# VCO_4046_v_2.net
KiCad netlist of a schematic drawn in EasyEDA
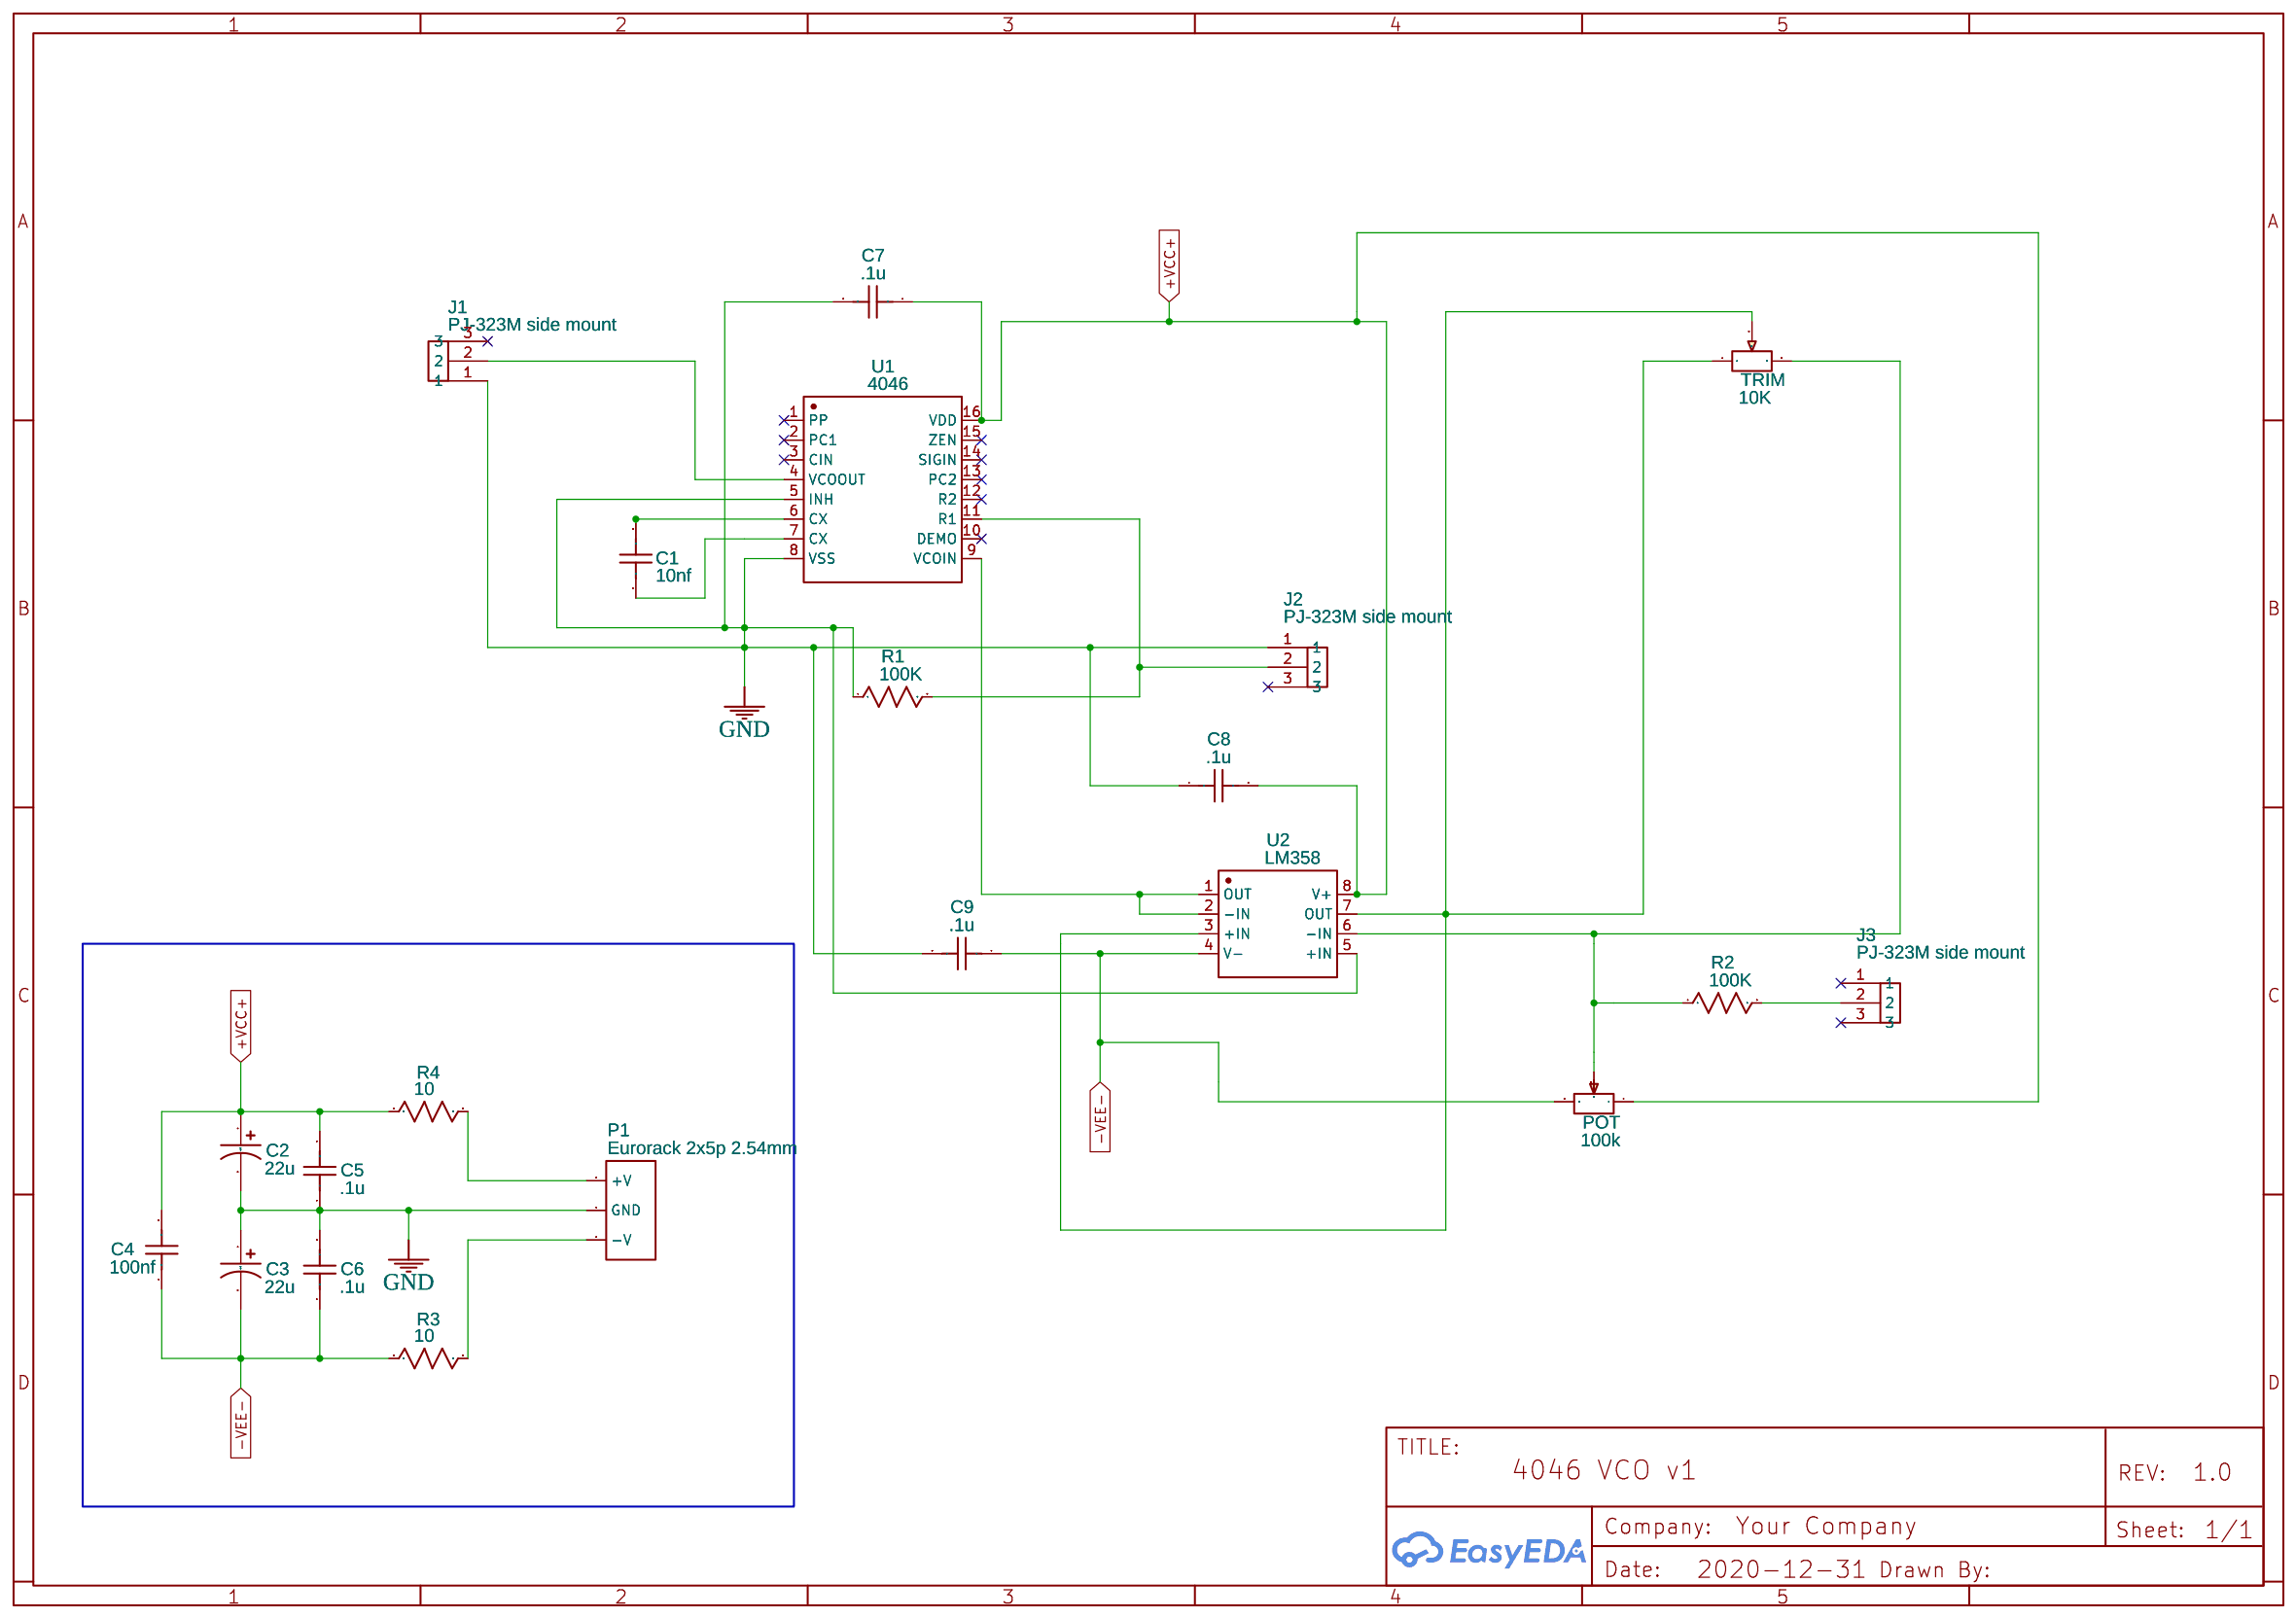
[diagram p0: schematic sheet]

(export (version "E")
  (design (tool "Eeschema 10.0.6"))
  (components
    (comp (ref "C1") (value "10nf") (libsource (lib "") (part "C_RAD-0.1_US_1")))
    (comp (ref "C2") (value "22u") (libsource (lib "") (part "CE_TH_D5.0×F2.0_US")))
    (comp (ref "C3") (value "22u") (libsource (lib "") (part "CE_TH_D5.0×F2.0_US")))
    (comp (ref "C4") (value "100nf") (libsource (lib "") (part "C_RAD-0.1_US_1")))
    (comp (ref "C5") (value ".1u") (libsource (lib "") (part "C_RAD-0.1_US_1")))
    (comp (ref "C6") (value ".1u") (libsource (lib "") (part "C_RAD-0.1_US_1")))
    (comp (ref "C7") (value ".1u") (libsource (lib "") (part "C_RAD-0.1_US")))
    (comp (ref "C8") (value ".1u") (libsource (lib "") (part "C_RAD-0.1_US_2")))
    (comp (ref "C9") (value ".1u") (libsource (lib "") (part "C_RAD-0.1_US")))
    (comp (ref "J1")
      (value "PJ-323M side mount")
      (fields (field (name "BOM_Manufacturer Part") "PJ-323M"))
      (libsource (lib "") (part "PJ-323M side mount"))
    )
    (comp (ref "J2")
      (value "PJ-323M side mount")
      (fields (field (name "BOM_Manufacturer Part") "PJ-323M"))
      (libsource (lib "") (part "PJ-323M side mount_1"))
    )
    (comp (ref "J3")
      (value "PJ-323M side mount")
      (fields (field (name "BOM_Manufacturer Part") "PJ-323M"))
      (libsource (lib "") (part "PJ-323M side mount_1"))
    )
    (comp (ref "P1")
      (value "Eurorack 2x5p 2.54mm")
      (fields
        (field (name "BOM_Manufacturer Part") "IDC Box 2.54mm 2X5P")
        (field (name "BOM_Supplier Part") "C5665")
      )
      (libsource (lib "") (part "Eurorack 2x5p 2.54mm"))
    )
    (comp (ref "POT")
      (value "100k")
      (fields
        (field (name "BOM_Manufacturer Part") "RK1631110U1Q")
        (field (name "BOM_Supplier Part") "C370978")
      )
      (libsource (lib "") (part "RK1631110U1Q"))
    )
    (comp (ref "R1") (value "100K") (libsource (lib "") (part "R_AXIAL-0.5_US")))
    (comp (ref "R2") (value "100K") (libsource (lib "") (part "R_AXIAL-0.5_US")))
    (comp (ref "R3") (value "10") (libsource (lib "") (part "R_AXIAL-0.5_US")))
    (comp (ref "R4") (value "10") (libsource (lib "") (part "R_AXIAL-0.5_US")))
    (comp (ref "TRIM")
      (value "10K")
      (fields
        (field (name "BOM_Manufacturer Part") "3386P-1-103")
        (field (name "BOM_Supplier Part") "C118953")
      )
      (libsource (lib "") (part "3386P-1-103_C118953"))
    )
    (comp (ref "U1") (value "4046") (libsource (lib "") (part "4046")))
    (comp (ref "U2") (value "LM358") (libsource (lib "") (part "LM358")))
  )
  (nets
    (net (code "1") (name "+VCC+") (class "Default")
      (node (ref "C2") (pin "1") (pinfunction "1_1") (pintype "unspecified"))
      (node (ref "C4") (pin "2") (pinfunction "2_2") (pintype "unspecified"))
      (node (ref "C5") (pin "2") (pinfunction "2_2") (pintype "unspecified"))
      (node (ref "C7") (pin "1") (pinfunction "1_1") (pintype "unspecified"))
      (node (ref "C8") (pin "2") (pinfunction "2_2") (pintype "unspecified"))
      (node (ref "POT") (pin "1") (pinfunction "1_1") (pintype "input"))
      (node (ref "R4") (pin "1") (pinfunction "1_1") (pintype "unspecified"))
      (node (ref "U1") (pin "16") (pinfunction "VDD_16") (pintype "unspecified"))
      (node (ref "U2") (pin "8") (pinfunction "V+_8") (pintype "unspecified"))
    )
    (net (code "2") (name "-VEE-") (class "Default")
      (node (ref "C3") (pin "2") (pinfunction "2_2") (pintype "unspecified"))
      (node (ref "C4") (pin "1") (pinfunction "1_1") (pintype "unspecified"))
      (node (ref "C6") (pin "1") (pinfunction "1_1") (pintype "unspecified"))
      (node (ref "C9") (pin "1") (pinfunction "1_1") (pintype "unspecified"))
      (node (ref "POT") (pin "3") (pinfunction "3_3") (pintype "input"))
      (node (ref "R3") (pin "1") (pinfunction "1_1") (pintype "unspecified"))
      (node (ref "U2") (pin "4") (pinfunction "V-_4") (pintype "unspecified"))
    )
    (net (code "3") (name "GND") (class "Default")
      (node (ref "C2") (pin "2") (pinfunction "2_2") (pintype "unspecified"))
      (node (ref "C3") (pin "1") (pinfunction "1_1") (pintype "unspecified"))
      (node (ref "C5") (pin "1") (pinfunction "1_1") (pintype "unspecified"))
      (node (ref "C6") (pin "2") (pinfunction "2_2") (pintype "unspecified"))
      (node (ref "C7") (pin "2") (pinfunction "2_2") (pintype "unspecified"))
      (node (ref "C8") (pin "1") (pinfunction "1_1") (pintype "unspecified"))
      (node (ref "C9") (pin "2") (pinfunction "2_2") (pintype "unspecified"))
      (node (ref "J1") (pin "1") (pinfunction "1_1") (pintype "unspecified"))
      (node (ref "J2") (pin "1") (pinfunction "1_1") (pintype "unspecified"))
      (node (ref "P1") (pin "2") (pinfunction "GND_2") (pintype "unspecified"))
      (node (ref "R1") (pin "1") (pinfunction "1_1") (pintype "unspecified"))
      (node (ref "U1") (pin "5") (pinfunction "INH_5") (pintype "unspecified"))
      (node (ref "U1") (pin "8") (pinfunction "VSS_8") (pintype "unspecified"))
      (node (ref "U2") (pin "5") (pinfunction "+IN_5") (pintype "unspecified"))
    )
    (net (code "4") (name "Net-(C1-Pad1)") (class "Default")
      (node (ref "C1") (pin "1") (pinfunction "1_1") (pintype "unspecified"))
      (node (ref "U1") (pin "7") (pinfunction "CX_7") (pintype "unspecified"))
    )
    (net (code "5") (name "Net-(C1-Pad2)") (class "Default")
      (node (ref "C1") (pin "2") (pinfunction "2_2") (pintype "unspecified"))
      (node (ref "U1") (pin "6") (pinfunction "CX_6") (pintype "unspecified"))
    )
    (net (code "6") (name "Net-(J3-Pad2)") (class "Default")
      (node (ref "J3") (pin "2") (pinfunction "2_2") (pintype "unspecified"))
      (node (ref "R2") (pin "2") (pinfunction "2_2") (pintype "unspecified"))
    )
    (net (code "7") (name "Net-(P1-+V)") (class "Default")
      (node (ref "P1") (pin "3") (pinfunction "+V_3") (pintype "unspecified"))
      (node (ref "R4") (pin "2") (pinfunction "2_2") (pintype "unspecified"))
    )
    (net (code "8") (name "Net-(P1--V)") (class "Default")
      (node (ref "P1") (pin "1") (pinfunction "-V_1") (pintype "unspecified"))
      (node (ref "R3") (pin "2") (pinfunction "2_2") (pintype "unspecified"))
    )
    (net (code "9") (name "Net-(POT-Pad2)") (class "Default")
      (node (ref "POT") (pin "2") (pinfunction "2_2") (pintype "input"))
      (node (ref "R2") (pin "1") (pinfunction "1_1") (pintype "unspecified"))
      (node (ref "TRIM") (pin "3") (pinfunction "3_3") (pintype "input"))
      (node (ref "U2") (pin "6") (pinfunction "-IN_6") (pintype "unspecified"))
    )
    (net (code "10") (name "Net-(TRIM-Pad1)") (class "Default")
      (node (ref "TRIM") (pin "1") (pinfunction "1_1") (pintype "input"))
      (node (ref "TRIM") (pin "2") (pinfunction "2_2") (pintype "input"))
      (node (ref "U2") (pin "3") (pinfunction "+IN_3") (pintype "unspecified"))
      (node (ref "U2") (pin "7") (pinfunction "OUT_7") (pintype "unspecified"))
    )
    (net (code "11") (name "Net-(U1-R1)") (class "Default")
      (node (ref "J2") (pin "2") (pinfunction "2_2") (pintype "unspecified"))
      (node (ref "R1") (pin "2") (pinfunction "2_2") (pintype "unspecified"))
      (node (ref "U1") (pin "11") (pinfunction "R1_11") (pintype "unspecified"))
    )
    (net (code "12") (name "Net-(U1-VCOIN)") (class "Default")
      (node (ref "U1") (pin "9") (pinfunction "VCOIN_9") (pintype "unspecified"))
      (node (ref "U2") (pin "1") (pinfunction "OUT_1") (pintype "unspecified"))
      (node (ref "U2") (pin "2") (pinfunction "-IN_2") (pintype "unspecified"))
    )
    (net (code "13") (name "Net-(U1-VCOOUT)") (class "Default")
      (node (ref "J1") (pin "2") (pinfunction "2_2") (pintype "unspecified"))
      (node (ref "U1") (pin "4") (pinfunction "VCOOUT_4") (pintype "unspecified"))
    )
    (net (code "14") (name "unconnected-(J1-Pad3)") (class "Default")
      (node (ref "J1") (pin "3") (pinfunction "3_3") (pintype "unspecified+no_connect"))
    )
    (net (code "15") (name "unconnected-(J2-Pad3)") (class "Default")
      (node (ref "J2") (pin "3") (pinfunction "3_3") (pintype "unspecified+no_connect"))
    )
    (net (code "16") (name "unconnected-(J3-Pad1)") (class "Default")
      (node (ref "J3") (pin "1") (pinfunction "1_1") (pintype "unspecified+no_connect"))
    )
    (net (code "17") (name "unconnected-(J3-Pad3)") (class "Default")
      (node (ref "J3") (pin "3") (pinfunction "3_3") (pintype "unspecified+no_connect"))
    )
    (net (code "18") (name "unconnected-(U1-CIN-Pad3)") (class "Default")
      (node (ref "U1") (pin "3") (pinfunction "CIN_3") (pintype "unspecified+no_connect"))
    )
    (net (code "19") (name "unconnected-(U1-DEMO-Pad10)") (class "Default")
      (node (ref "U1") (pin "10") (pinfunction "DEMO_10") (pintype "unspecified+no_connect"))
    )
    (net (code "20") (name "unconnected-(U1-PC1-Pad2)") (class "Default")
      (node (ref "U1") (pin "2") (pinfunction "PC1_2") (pintype "unspecified+no_connect"))
    )
    (net (code "21") (name "unconnected-(U1-PC2-Pad13)") (class "Default")
      (node (ref "U1") (pin "13") (pinfunction "PC2_13") (pintype "unspecified+no_connect"))
    )
    (net (code "22") (name "unconnected-(U1-PP-Pad1)") (class "Default")
      (node (ref "U1") (pin "1") (pinfunction "PP_1") (pintype "unspecified+no_connect"))
    )
    (net (code "23") (name "unconnected-(U1-R2-Pad12)") (class "Default")
      (node (ref "U1") (pin "12") (pinfunction "R2_12") (pintype "unspecified+no_connect"))
    )
    (net (code "24") (name "unconnected-(U1-SIGIN-Pad14)") (class "Default")
      (node (ref "U1") (pin "14") (pinfunction "SIGIN_14") (pintype "unspecified+no_connect"))
    )
    (net (code "25") (name "unconnected-(U1-ZEN-Pad15)") (class "Default")
      (node (ref "U1") (pin "15") (pinfunction "ZEN_15") (pintype "unspecified+no_connect"))
    )
  )
)
